# 2_Input.net
KiCad netlist of a schematic drawn in Altium Designer
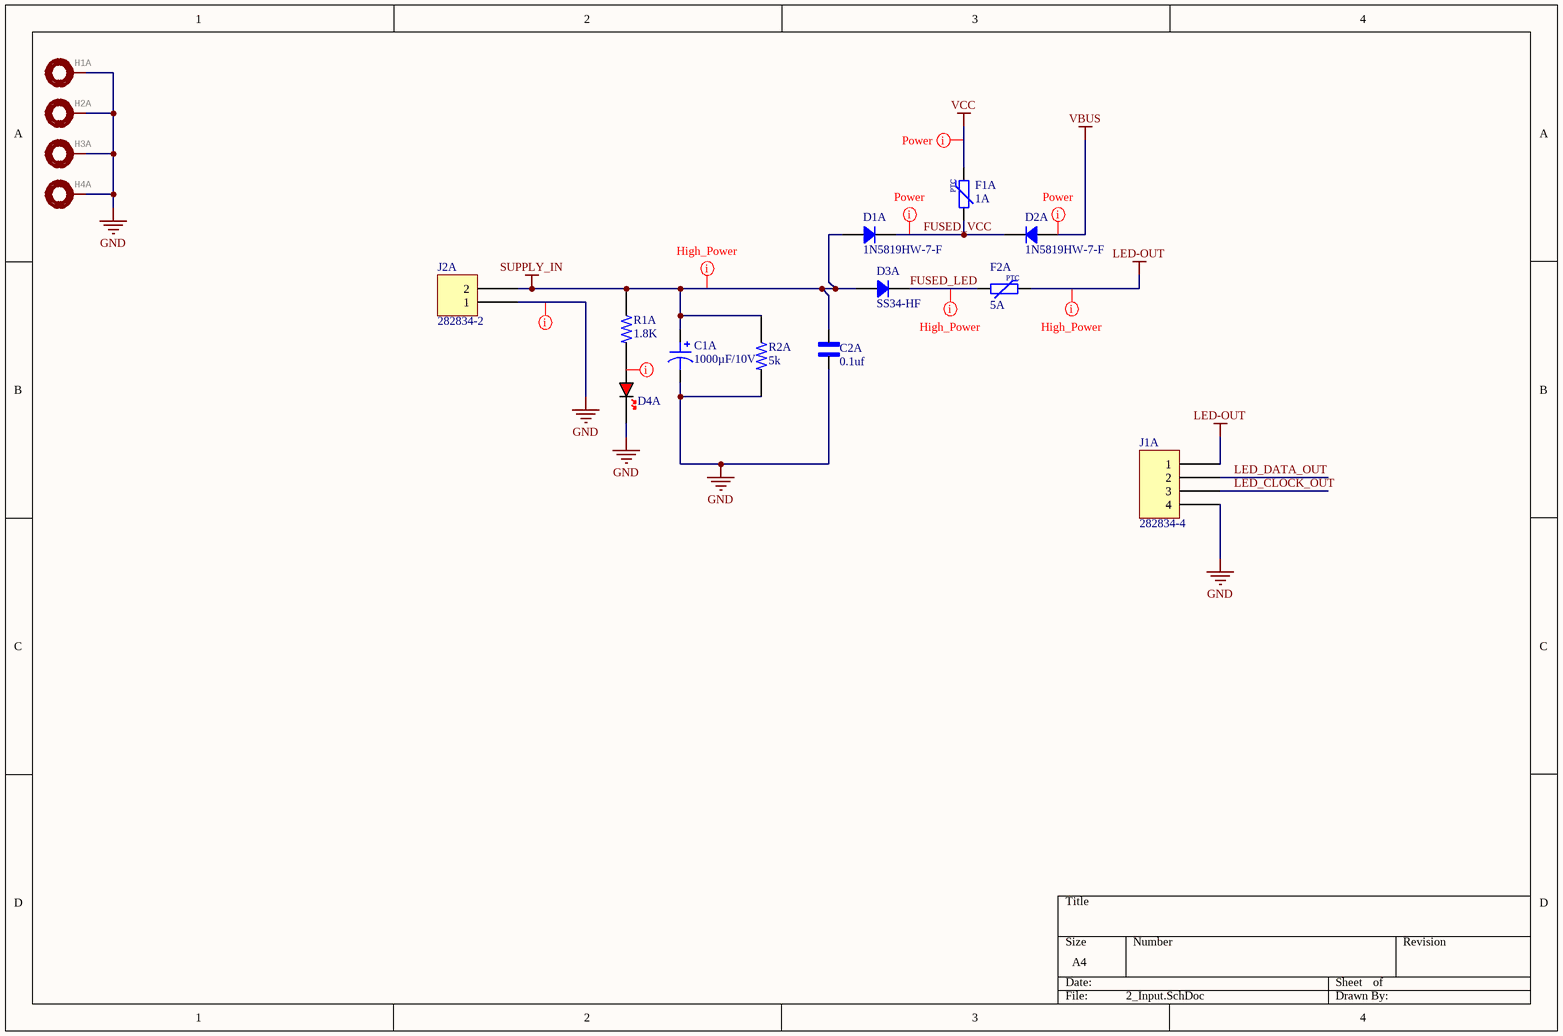
[diagram p0: 2_Input.SchDoc]

(export (version "E")
  (design (tool "Eeschema 10.0.6"))
  (components
    (comp (ref "C1A")
      (value "1000µF/10V")
      (footprint "CAP TH ALUM ELEC D8.00mm S3.50mm H13.00mm")
      (description "CAP ALUM 1000UF 20% 10V RADIAL")
      (fields (field (name "PART NUMBER") "10PK1000MEFC8X11.5") (field (name "MANUFACTURER") "Rubycon"))
      (libsource (lib "ESP01-S-UART") (part "Polarised Capacitor"))
    )
    (comp (ref "C2A")
      (value "0.1uf")
      (footprint "C-0603")
      (description "Ceramic Capacitor 16V 0603 (1608 Metric)")
      (fields (field (name "MP") "C0603C104J4RAC") (field (name "MF") "KEMET"))
      (libsource (lib "ESP01-S-UART") (part "C-0603"))
    )
    (comp (ref "D1A")
      (value "1N5819HW-7-F")
      (footprint "SOD-123")
      (description "DIODE SCHOTTKY 40V 1A SOD123")
      (fields (field (name "MANUFACTURER") "Diodes Incorporated"))
      (libsource (lib "ESP01-S-UART") (part "Diode"))
    )
    (comp (ref "D2A")
      (value "1N5819HW-7-F")
      (footprint "SOD-123")
      (description "DIODE SCHOTTKY 40V 1A SOD123")
      (fields (field (name "MANUFACTURER") "Diodes Incorporated"))
      (libsource (lib "ESP01-S-UART") (part "Diode"))
    )
    (comp (ref "D3A")
      (value "SS34-HF")
      (footprint "DO214AC SMA")
      (description "DIODE SCHOTTKY 40V 3A DO214AC SM")
      (fields (field (name "MANUFACTURER") "Comchip Technology"))
      (libsource (lib "ESP01-S-UART") (part "Diode"))
    )
    (comp (ref "D4A")
      (value "RED")
      (footprint "LED_0603_RED")
      (description "LED 0603 RED SMD")
      (libsource (lib "ESP01-S-UART") (part "LED_0603_RED"))
    )
    (comp (ref "F1A")
      (value "1A")
      (footprint "FUSE_1206")
      (description "Fuse PPTC SMD 1206")
      (libsource (lib "ESP01-S-UART") (part "FUSE_PPTC_1206"))
    )
    (comp (ref "F2A")
      (value "5A")
      (footprint "FUSE_1206")
      (description "Fuse PPTC SMD 1206")
      (libsource (lib "ESP01-S-UART") (part "FUSE_PPTC_1206"))
    )
    (comp (ref "H1A")
      (value "MOUNTING PAD, round")
      (footprint "2,8-PAD")
      (libsource (lib "ESP01-S-UART") (part "MOUNT-PAD-ROUND2.8"))
    )
    (comp (ref "H2A")
      (value "MOUNTING PAD, round")
      (footprint "2,8-PAD")
      (libsource (lib "ESP01-S-UART") (part "MOUNT-PAD-ROUND2.8"))
    )
    (comp (ref "H3A")
      (value "MOUNTING PAD, round")
      (footprint "2,8-PAD")
      (libsource (lib "ESP01-S-UART") (part "MOUNT-PAD-ROUND2.8"))
    )
    (comp (ref "H4A")
      (value "MOUNTING PAD, round")
      (footprint "2,8-PAD")
      (libsource (lib "ESP01-S-UART") (part "MOUNT-PAD-ROUND2.8"))
    )
    (comp (ref "J1A")
      (value "282834-4")
      (footprint "TE 282834-4")
      (description "TERM BLK 4P SIDE ENT 2.54MM PCB")
      (fields (field (name "MANUFACTURER") "TE Connectivity AMP Connectors") (field (name "VOLTAGE") "150V"))
      (libsource (lib "ESP01-S-UART") (part "4 Pin"))
    )
    (comp (ref "J2A")
      (value "282834-2")
      (footprint "TE 282834-2")
      (description "TERM BLK 2P SIDE ENT 2.54MM PCB")
      (fields (field (name "MANUFACTURER") "TE Connectivity AMP Connectors") (field (name "VOLTAGE") "150V"))
      (libsource (lib "ESP01-S-UART") (part "2 Pin"))
    )
    (comp (ref "R1A")
      (value "1.8K")
      (footprint "R-0603")
      (description "0603")
      (fields (field (name "MP") "2-1623703-0") (field (name "TOLERANCE") "1%"))
      (libsource (lib "ESP01-S-UART") (part "R-0603"))
    )
    (comp (ref "R2A")
      (value "5k")
      (footprint "R-0603")
      (description "0603")
      (fields (field (name "MP") "2-1623703-0") (field (name "TOLERANCE") "1%"))
      (libsource (lib "ESP01-S-UART") (part "R-0603"))
    )
  )
  (nets
    (net (code "1") (name "/FUSED_LED") (class "Default")
      (node (ref "D3A") (pin "2") (pinfunction "2_2") (pintype "passive"))
      (node (ref "F2A") (pin "1") (pinfunction "1_1") (pintype "passive"))
    )
    (net (code "2") (name "/FUSED_VCC") (class "Default")
      (node (ref "D1A") (pin "2") (pinfunction "2_2") (pintype "passive"))
      (node (ref "D2A") (pin "2") (pinfunction "2_2") (pintype "passive"))
      (node (ref "F1A") (pin "1") (pinfunction "1_1") (pintype "passive"))
    )
    (net (code "3") (name "/LED_CLOCK_OUT") (class "Default")
      (node (ref "J1A") (pin "3") (pinfunction "3_3") (pintype "passive"))
    )
    (net (code "4") (name "/LED_DATA_OUT") (class "Default")
      (node (ref "J1A") (pin "2") (pinfunction "2_2") (pintype "passive"))
    )
    (net (code "5") (name "GND") (class "Default")
      (node (ref "C1A") (pin "2") (pinfunction "2_2") (pintype "passive"))
      (node (ref "C2A") (pin "1") (pinfunction "1_1") (pintype "passive"))
      (node (ref "D4A") (pin "K") (pinfunction "K_K") (pintype "passive"))
      (node (ref "H1A") (pin "1") (pinfunction "MOUNT_1") (pintype "passive"))
      (node (ref "H2A") (pin "1") (pinfunction "MOUNT_1") (pintype "passive"))
      (node (ref "H3A") (pin "1") (pinfunction "MOUNT_1") (pintype "passive"))
      (node (ref "H4A") (pin "1") (pinfunction "MOUNT_1") (pintype "passive"))
      (node (ref "J1A") (pin "4") (pinfunction "4_4") (pintype "passive"))
      (node (ref "J2A") (pin "1") (pinfunction "1_1") (pintype "passive"))
      (node (ref "R2A") (pin "2") (pinfunction "2_2") (pintype "passive"))
    )
    (net (code "6") (name "LED-OUT") (class "Default")
      (node (ref "F2A") (pin "2") (pinfunction "2_2") (pintype "passive"))
      (node (ref "J1A") (pin "1") (pinfunction "1_1") (pintype "passive"))
    )
    (net (code "7") (name "Net-(D4A-PadA)") (class "Default")
      (node (ref "D4A") (pin "A") (pinfunction "A_A") (pintype "passive"))
      (node (ref "R1A") (pin "2") (pinfunction "2_2") (pintype "passive"))
    )
    (net (code "8") (name "SUPPLY_IN") (class "Default")
      (node (ref "C1A") (pin "1") (pinfunction "1_1") (pintype "passive"))
      (node (ref "C2A") (pin "2") (pinfunction "2_2") (pintype "passive"))
      (node (ref "D1A") (pin "1") (pinfunction "1_1") (pintype "passive"))
      (node (ref "D3A") (pin "1") (pinfunction "1_1") (pintype "passive"))
      (node (ref "J2A") (pin "2") (pinfunction "2_2") (pintype "passive"))
      (node (ref "R1A") (pin "1") (pinfunction "1_1") (pintype "passive"))
      (node (ref "R2A") (pin "1") (pinfunction "1_1") (pintype "passive"))
    )
    (net (code "9") (name "VBUS") (class "Default")
      (node (ref "D2A") (pin "1") (pinfunction "1_1") (pintype "passive"))
    )
    (net (code "10") (name "VCC") (class "Default")
      (node (ref "F1A") (pin "2") (pinfunction "2_2") (pintype "passive"))
    )
  )
)
